# PICO_D4_SD_CARD_T3.net
KiCad netlist of a schematic drawn in Altium Designer
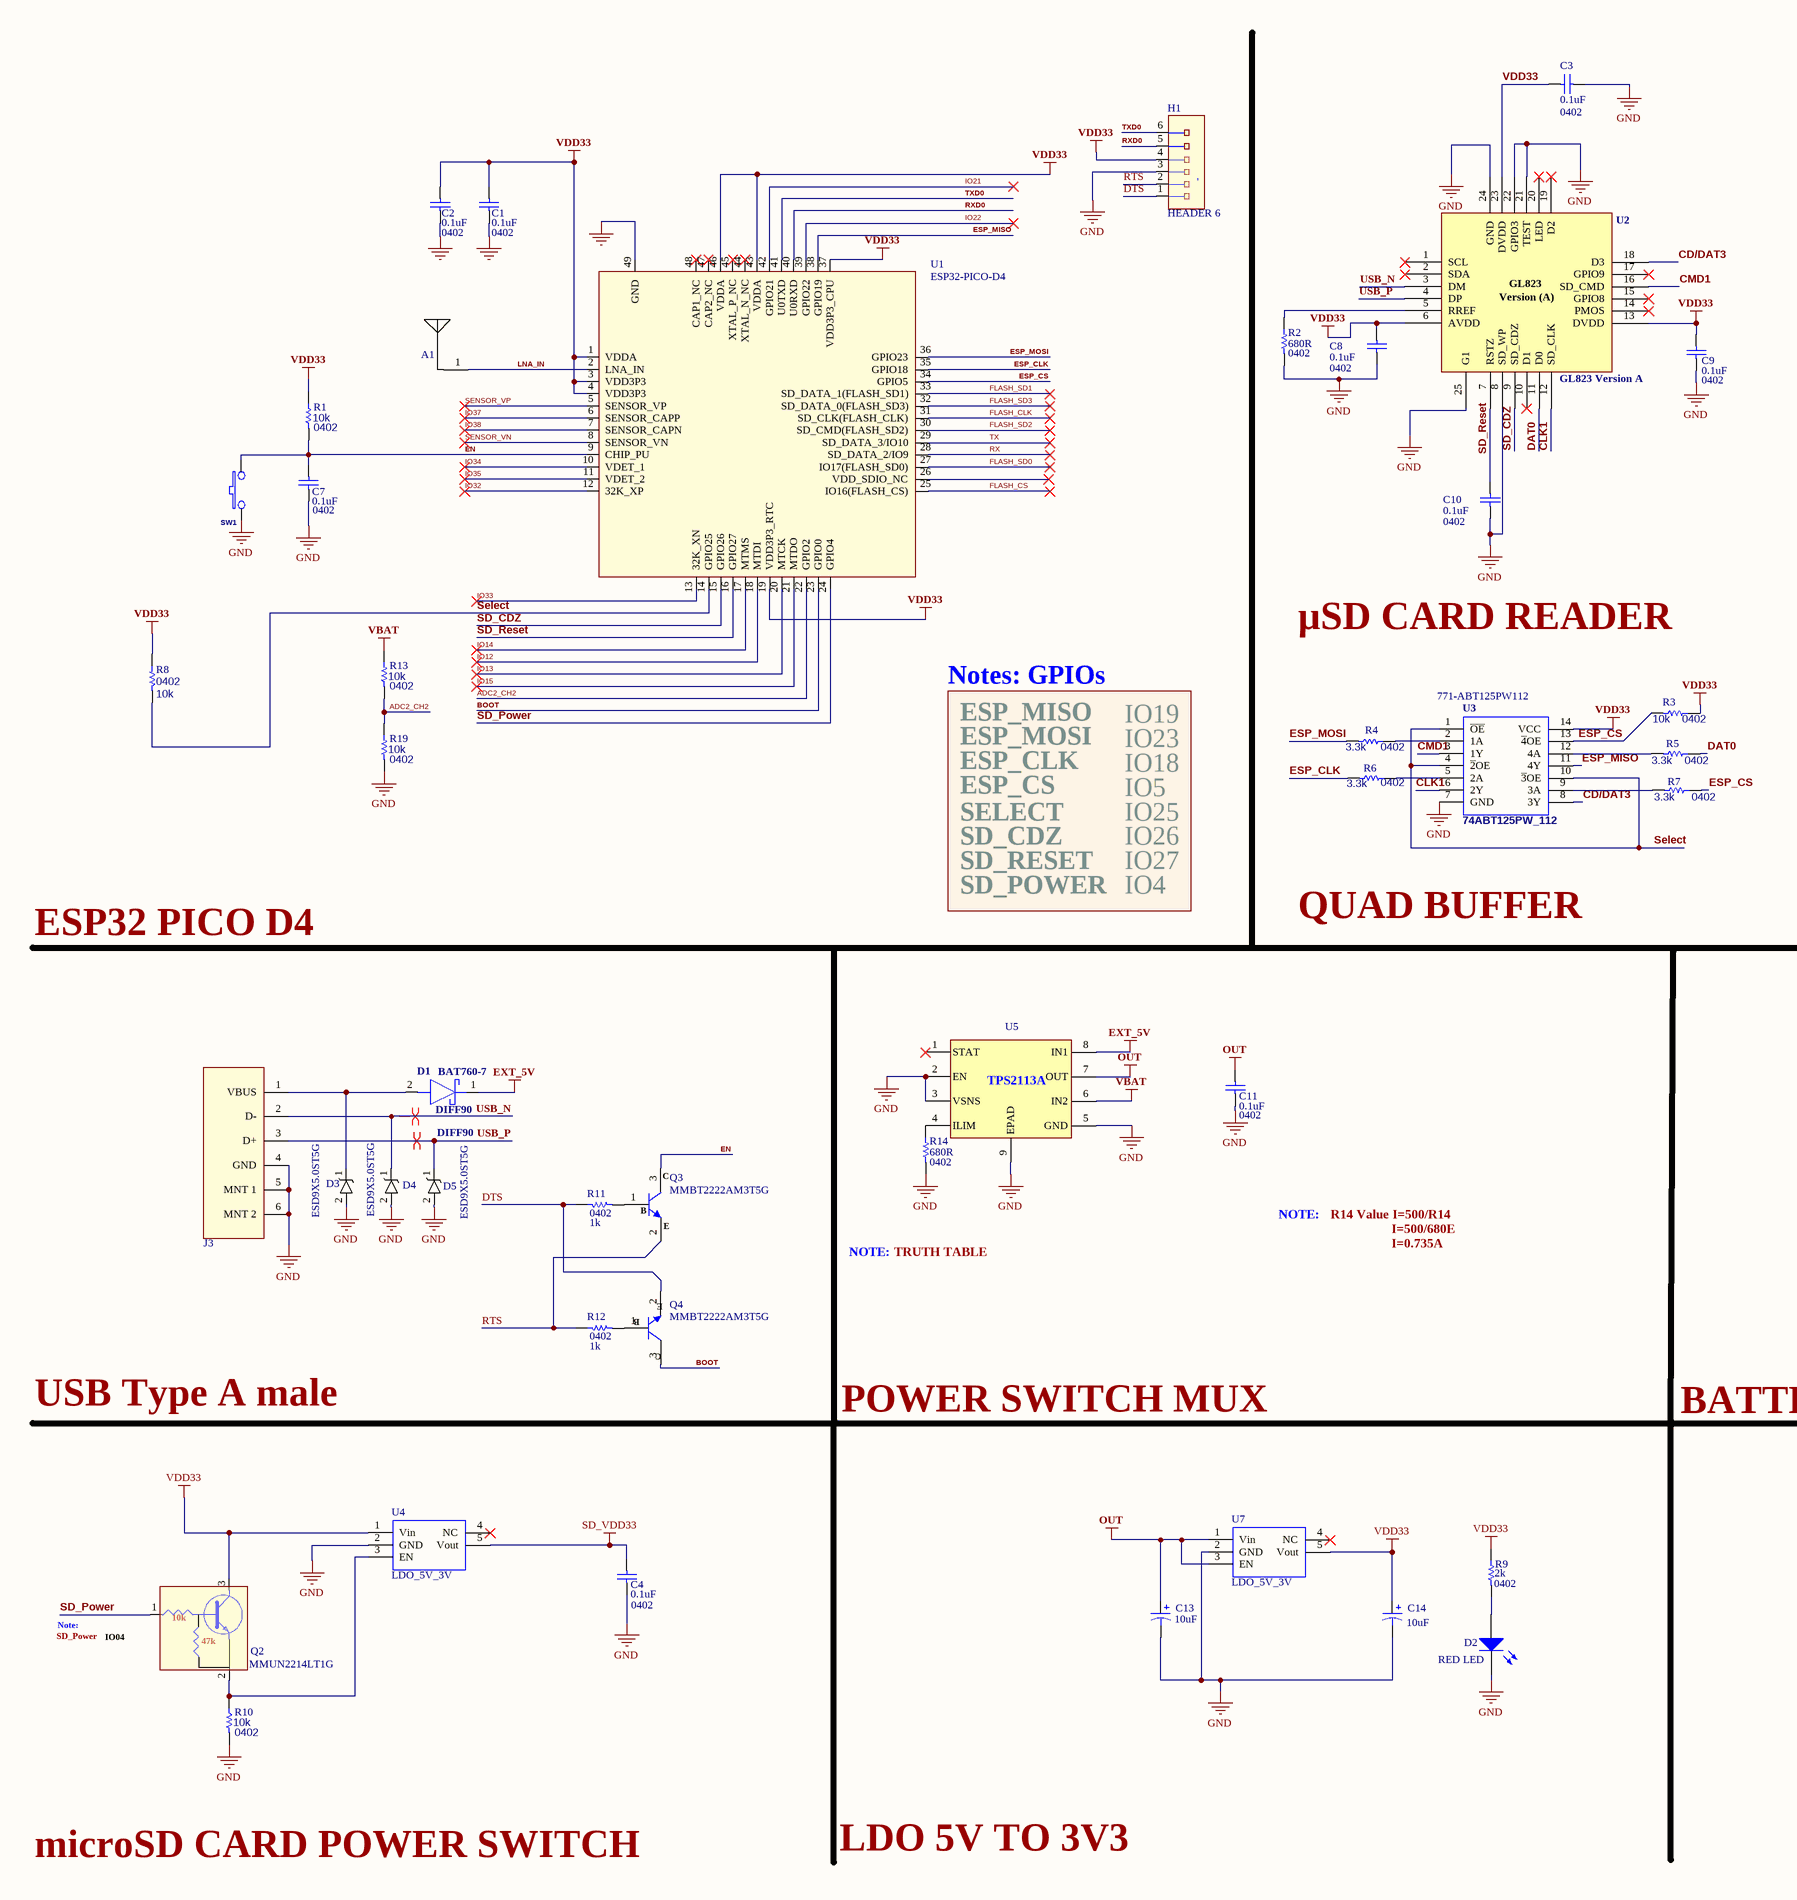
[diagram p0: PICO_D4_SD_CARD_T3.SchDoc, left]
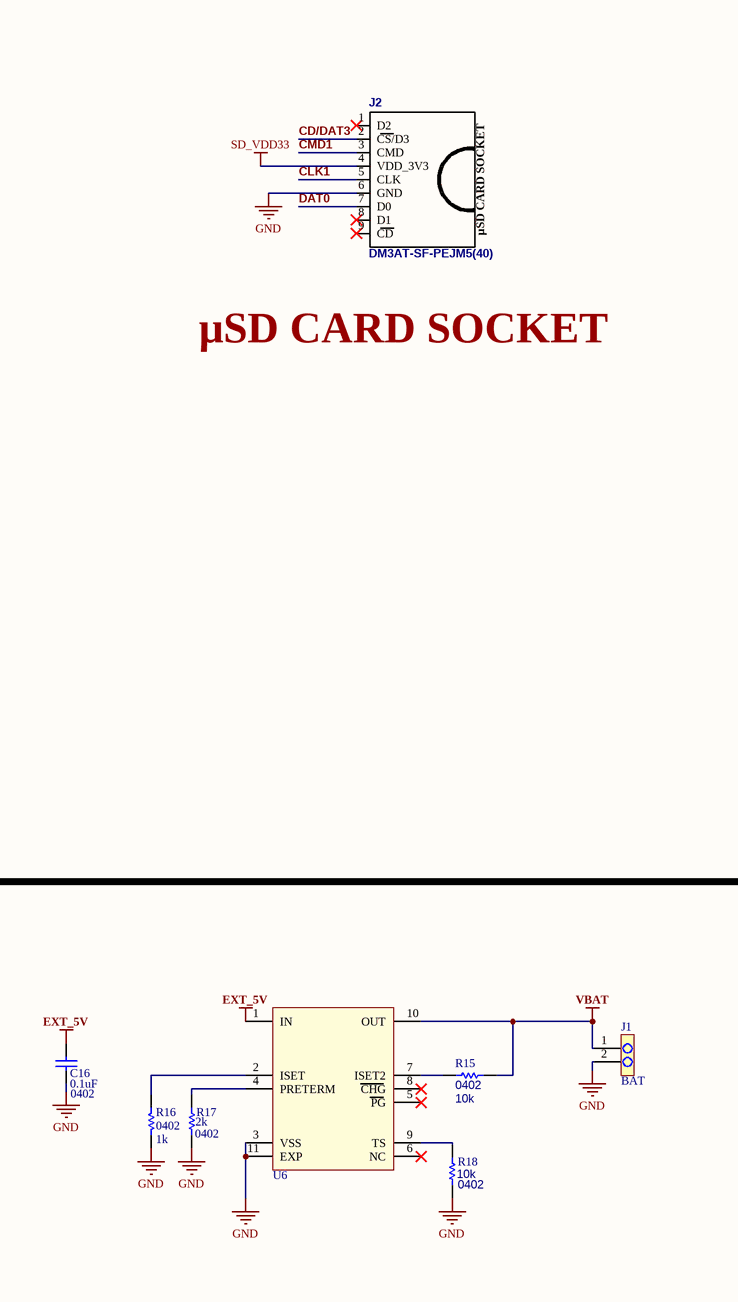
[diagram p1: PICO_D4_SD_CARD_T3.SchDoc, right]

(export (version "E")
  (design (tool "Eeschema 10.0.6"))
  (components
    (comp (ref "A1")
      (value "Ant")
      (footprint "ANT_2450AT43B100E")
      (description "High Frequency Ceramic Solutions 4-Pin SMD T/R")
      (fields
        (field (name "MANUFACTURER") "Johanson")
        (field (name "MANUFACTURER PART NUMBER") "2450AT43B100E")
      )
      (libsource (lib "CUSTOM TNY290PG") (part "Ant"))
    )
    (comp (ref "C1")
      (value "0.1uF")
      (footprint "CAPC0402")
      (description "Ceramic Capacitor,100nF,16V,0402")
      (fields
        (field (name "CASE/PACKAGE") "0402")
        (field (name "MFR.") "C0805C104K1RECAUTO")
        (field (name "MANUFACTURER") "TDK")
      )
      (libsource (lib "Miscellaneous Devices") (part "Cap"))
    )
    (comp (ref "C2")
      (value "0.1uF")
      (footprint "CAPC0402")
      (description "Ceramic Capacitor,100nF,16V,0402")
      (fields
        (field (name "CASE/PACKAGE") "0402")
        (field (name "MFR.") "C0805C104K1RECAUTO")
        (field (name "MANUFACTURER") "TDK")
      )
      (libsource (lib "Miscellaneous Devices") (part "Cap"))
    )
    (comp (ref "C3")
      (value "0.1uF")
      (footprint "CAPC0402")
      (description "Ceramic Capacitor,100nF,16V,0402")
      (fields
        (field (name "CASE/PACKAGE") "0402")
        (field (name "MFR.") "C0805C104K1RECAUTO")
        (field (name "MANUFACTURER") "TDK")
      )
      (libsource (lib "Miscellaneous Devices") (part "Cap"))
    )
    (comp (ref "C4")
      (value "0.1uF")
      (footprint "CAPC0402")
      (description "Ceramic Capacitor,100nF,16V,0402")
      (fields
        (field (name "CASE/PACKAGE") "0402")
        (field (name "MFR.") "C0805C104K1RECAUTO")
        (field (name "MANUFACTURER") "TDK")
      )
      (libsource (lib "Miscellaneous Devices") (part "Cap"))
    )
    (comp (ref "C7")
      (value "0.1uF")
      (footprint "CAPC0402")
      (description "Ceramic Capacitor,100nF,16V,0402")
      (fields
        (field (name "CASE/PACKAGE") "0402")
        (field (name "MFR.") "C0805C104K1RECAUTO")
        (field (name "MANUFACTURER") "TDK")
      )
      (libsource (lib "Miscellaneous Devices") (part "Cap"))
    )
    (comp (ref "C8")
      (value "0.1uF")
      (footprint "CAPC0402")
      (description "Ceramic Capacitor,100nF,16V,0402")
      (fields
        (field (name "CASE/PACKAGE") "0402")
        (field (name "MFR.") "C0805C104K1RECAUTO")
        (field (name "MANUFACTURER") "TDK")
      )
      (libsource (lib "Miscellaneous Devices") (part "Cap"))
    )
    (comp (ref "C9")
      (value "0.1uF")
      (footprint "CAPC0402")
      (description "Ceramic Capacitor,100nF,16V,0402")
      (fields
        (field (name "CASE/PACKAGE") "0402")
        (field (name "MFR.") "C0805C104K1RECAUTO")
        (field (name "MANUFACTURER") "TDK")
      )
      (libsource (lib "Miscellaneous Devices") (part "Cap"))
    )
    (comp (ref "C10")
      (value "0.1uF")
      (footprint "CAPC0402")
      (description "Ceramic Capacitor,100nF,16V,0402")
      (fields
        (field (name "CASE/PACKAGE") "0402")
        (field (name "MFR.") "C0805C104K1RECAUTO")
        (field (name "MANUFACTURER") "TDK")
      )
      (libsource (lib "Miscellaneous Devices") (part "Cap"))
    )
    (comp (ref "C11")
      (value "0.1uF")
      (footprint "CAPC0402")
      (description "Ceramic Capacitor,100nF,16V,0402")
      (fields
        (field (name "CASE/PACKAGE") "0402")
        (field (name "MFR.") "C0805C104K1RECAUTO")
        (field (name "MANUFACTURER") "TDK")
      )
      (libsource (lib "Miscellaneous Devices") (part "Cap"))
    )
    (comp (ref "C13")
      (value "10uF")
      (footprint "CAPC0603")
      (description "Ceramic Capacitor,10uF,16V,0603")
      (libsource (lib "Miscellaneous Devices") (part "Cap Pol2"))
    )
    (comp (ref "C14")
      (value "10uF")
      (footprint "CAPC0603")
      (description "Ceramic Capacitor,10uF,16V,0603")
      (libsource (lib "Miscellaneous Devices") (part "Cap Pol2"))
    )
    (comp (ref "C16")
      (value "0.1uF")
      (footprint "CAPC0402")
      (description "Ceramic Capacitor,100nF,16V,0402")
      (fields
        (field (name "CASE/PACKAGE") "0402")
        (field (name "MFR.") "C0805C104K1RECAUTO")
        (field (name "MANUFACTURER") "TDK")
      )
      (libsource (lib "Miscellaneous Devices") (part "Cap"))
    )
    (comp (ref "D1")
      (value "BAT760-7")
      (footprint "SOD2513X120N")
      (description "Schottky Diodes & Rectifiers 1A 30V LF1A, 2-Pin SOD-323")
      (libsource (lib "CUSTOM TNY290PG") (part "BAT760-7"))
    )
    (comp (ref "D2")
      (value "RED LED")
      (footprint "LED_0603")
      (description "LED, RED,SMD, 0603")
      (libsource (lib "Miscellaneous Devices") (part "LED1"))
    )
    (comp (ref "D3")
      (value "ESD9X5.0ST5G")
      (footprint "SOD-923")
      (description "12.3V Clamp 8.7A (8/20µs) Ipp Tvs Diode Surface Mount SOD-923")
      (fields
        (field (name "MANUFACTURER") "ON Semiconductor")
        (field (name "MANUFACTURER PART NUMBER") "ESD9X5.0ST5G")
      )
      (libsource (lib "CUSTOM TNY290PG") (part "ESD9X5.0ST5G"))
    )
    (comp (ref "D4")
      (value "ESD9X5.0ST5G")
      (footprint "SOD-923")
      (description "12.3V Clamp 8.7A (8/20µs) Ipp Tvs Diode Surface Mount SOD-923")
      (fields
        (field (name "MANUFACTURER") "ON Semiconductor")
        (field (name "MANUFACTURER PART NUMBER") "ESD9X5.0ST5G")
      )
      (libsource (lib "CUSTOM TNY290PG") (part "ESD9X5.0ST5G"))
    )
    (comp (ref "D5")
      (value "ESD9X5.0ST5G")
      (footprint "SOD-923")
      (description "12.3V Clamp 8.7A (8/20µs) Ipp Tvs Diode Surface Mount SOD-923")
      (fields
        (field (name "MANUFACTURER") "ON Semiconductor")
        (field (name "MANUFACTURER PART NUMBER") "ESD9X5.0ST5G")
      )
      (libsource (lib "CUSTOM TNY290PG") (part "ESD9X5.0ST5G"))
    )
    (comp (ref "H1")
      (value "HEADER 6")
      (footprint "HEADER_2MM")
      (description "Header, 6-Pin,2MM")
      (fields (field (name "MANUFACTURER PART NUMBER") "2mm PITCH"))
      (libsource (lib "CUSTOM TNY290PG") (part "HEADER 6"))
    )
    (comp (ref "J1")
      (value "BAT")
      (footprint "HDR1X2H - duplicate")
      (libsource (lib "CUSTOM TNY290PG") (part "Header 2 pin"))
    )
    (comp (ref "J2")
      (value "DM3AT-SF-PEJM5(40)")
      (footprint "sd card connector")
      (description "Micro SD Memory Card Socket")
      (fields
        (field (name "RS PART NUMBER") "7079520P")
        (field (name "MOUSER PART NUMBER") "798-DM3AT-SF-PEJM540")
      )
      (libsource (lib "CUSTOM TNY290PG") (part "DM3AT-SF-PEJM5(40)"))
    )
    (comp (ref "J3")
      (value "USB MALE")
      (footprint "Molex_48037-0001_0")
      (description "USB A-type Plug Male PCB R/A")
      (fields (field (name "MANUFACTURER PART NUMBER") "USB Type A male"))
      (libsource (lib "CUSTOM TNY290PG") (part "USB MALE"))
    )
    (comp (ref "Q2")
      (value "Transistor NPN")
      (footprint "SOT95P240X115-3N")
      (description "Bipolar Transistors - Pre-Biased 100mA 50V BRT NPN")
      (fields
        (field (name "MANUFACTURER") "ON Semiconductor")
        (field (name "MANUFACTURER PART NUMBER") "MMUN2214LT1G")
      )
      (libsource (lib "CUSTOM TNY290PG") (part "Transistor NPN"))
    )
    (comp (ref "Q3")
      (value "MMBT2222AM3T5G")
      (footprint "SOT-723")
      (description "Bipolar Transistors - BJT SS SOT-723 GP TRANSISTOR NPN")
      (fields (field (name "MANUFACTURER") "ON Semiconductor"))
      (libsource (lib "CUSTOM TNY290PG") (part "MMBT2222AM3T5G"))
    )
    (comp (ref "Q4")
      (value "MMBT2222AM3T5G")
      (footprint "SOT-723")
      (description "Bipolar Transistors - BJT SS SOT-723 GP TRANSISTOR NPN")
      (fields (field (name "MANUFACTURER") "ON Semiconductor"))
      (libsource (lib "CUSTOM TNY290PG") (part "MMBT2222AM3T5G"))
    )
    (comp (ref "R1")
      (value "10k")
      (footprint "resc0402")
      (description "Thick Film Resistor -  10Kohm, 1%, 0402")
      (fields
        (field (name "MANUFACTURER") "Vishay")
        (field (name "MANUFACTURER PART NUMBER") "CRCW040210K0FKED")
        (field (name "CASE/PACKAGE") "0402")
      )
      (libsource (lib "Miscellaneous Devices") (part "Res1"))
    )
    (comp (ref "R2")
      (value "680R")
      (footprint "resc0402")
      (description "Thick Film Resistor - 680 ohm, 1%, 0402")
      (fields
        (field (name "MANUFACTURER") "Panasonic")
        (field (name "MANUFACTURER PART NUMBER") "ERA-2AEB681X")
        (field (name "CASE/PACKAGE") "0402")
      )
      (libsource (lib "Miscellaneous Devices") (part "Res1"))
    )
    (comp (ref "R3")
      (value "10k")
      (footprint "resc0402")
      (description "Thick Film Resistor -  10Kohm, 1%, 0402")
      (fields
        (field (name "MANUFACTURER") "Vishay")
        (field (name "MANUFACTURER PART NUMBER") "CRCW040210K0FKED")
        (field (name "CASE/PACKAGE") "0402")
      )
      (libsource (lib "Miscellaneous Devices") (part "Res1"))
    )
    (comp (ref "R4")
      (value "3.3k")
      (footprint "RESC0402")
      (description "Thick Film Resistor - 3.3 Kohm, 1%, 0402")
      (fields
        (field (name "MANUFACTURER") "Vishay Dale")
        (field (name "MANUFACTURER PART NUMBER") "CRCW04023K30JNED")
        (field (name "CASE/PACKAGE") "0402")
      )
      (libsource (lib "Miscellaneous Devices") (part "Res1"))
    )
    (comp (ref "R5")
      (value "3.3k")
      (footprint "RESC0402")
      (description "Thick Film Resistor - 3.3 Kohm, 1%, 0402")
      (fields
        (field (name "MANUFACTURER") "Vishay Dale")
        (field (name "MANUFACTURER PART NUMBER") "CRCW04023K30JNED")
        (field (name "CASE/PACKAGE") "0402")
      )
      (libsource (lib "Miscellaneous Devices") (part "Res1"))
    )
    (comp (ref "R6")
      (value "3.3k")
      (footprint "RESC0402")
      (description "Thick Film Resistor - 3.3 Kohm, 1%, 0402")
      (fields
        (field (name "MANUFACTURER") "Vishay Dale")
        (field (name "MANUFACTURER PART NUMBER") "CRCW04023K30JNED")
        (field (name "CASE/PACKAGE") "0402")
      )
      (libsource (lib "Miscellaneous Devices") (part "Res1"))
    )
    (comp (ref "R7")
      (value "3.3k")
      (footprint "RESC0402")
      (description "Thick Film Resistor - 3.3 Kohm, 1%, 0402")
      (fields
        (field (name "MANUFACTURER") "Vishay Dale")
        (field (name "MANUFACTURER PART NUMBER") "CRCW04023K30JNED")
        (field (name "CASE/PACKAGE") "0402")
      )
      (libsource (lib "Miscellaneous Devices") (part "Res1"))
    )
    (comp (ref "R8")
      (value "10k")
      (footprint "resc0402")
      (description "Thick Film Resistor -  10Kohm, 1%, 0402")
      (fields
        (field (name "MANUFACTURER") "Vishay")
        (field (name "MANUFACTURER PART NUMBER") "CRCW040210K0FKED")
        (field (name "CASE/PACKAGE") "0402")
      )
      (libsource (lib "Miscellaneous Devices") (part "Res1"))
    )
    (comp (ref "R9")
      (value "2k")
      (footprint "resc0402")
      (description "Thick Film Resistor -  2Kohm, 1%, 0402")
      (fields
        (field (name "MANUFACTURER") "Vishay Semiconductors")
        (field (name "MANUFACTURER PART NUMBER") "CRCW04022K00FKEDC")
        (field (name "CASE/PACKAGE") "0402")
      )
      (libsource (lib "Miscellaneous Devices") (part "Res1"))
    )
    (comp (ref "R10")
      (value "10k")
      (footprint "resc0402")
      (description "Thick Film Resistor -  10Kohm, 1%, 0402")
      (fields
        (field (name "MANUFACTURER") "Vishay")
        (field (name "MANUFACTURER PART NUMBER") "CRCW040210K0FKED")
        (field (name "CASE/PACKAGE") "0402")
      )
      (libsource (lib "Miscellaneous Devices") (part "Res1"))
    )
    (comp (ref "R11")
      (value "1k")
      (footprint "resc0402")
      (description "Thick Film Resistor -  1Kohm, 1%, 0402")
      (fields
        (field (name "MANUFACTURER") "TE Connectivity")
        (field (name "MANUFACTURER PART NUMBER") "CRGCQ0402F1K0")
        (field (name "CASE/PACKAGE") "0402")
      )
      (libsource (lib "Miscellaneous Devices") (part "Res1"))
    )
    (comp (ref "R12")
      (value "1k")
      (footprint "resc0402")
      (description "Thick Film Resistor -  1Kohm, 1%, 0402")
      (fields
        (field (name "MANUFACTURER") "TE Connectivity")
        (field (name "MANUFACTURER PART NUMBER") "CRGCQ0402F1K0")
        (field (name "CASE/PACKAGE") "0402")
      )
      (libsource (lib "Miscellaneous Devices") (part "Res1"))
    )
    (comp (ref "R13")
      (value "10k")
      (footprint "resc0402")
      (description "Thick Film Resistor -  10Kohm, 1%, 0402")
      (fields
        (field (name "MANUFACTURER") "Vishay")
        (field (name "MANUFACTURER PART NUMBER") "CRCW040210K0FKED")
        (field (name "CASE/PACKAGE") "0402")
      )
      (libsource (lib "Miscellaneous Devices") (part "Res1"))
    )
    (comp (ref "R14")
      (value "680R")
      (footprint "resc0402")
      (description "Thick Film Resistor - 680 ohm, 1%, 0402")
      (fields
        (field (name "MANUFACTURER") "Panasonic")
        (field (name "MANUFACTURER PART NUMBER") "ERA-2AEB681X")
        (field (name "CASE/PACKAGE") "0402")
      )
      (libsource (lib "Miscellaneous Devices") (part "Res1"))
    )
    (comp (ref "R15")
      (value "10k")
      (footprint "resc0402")
      (description "Thick Film Resistor -  10Kohm, 1%, 0402")
      (fields
        (field (name "MANUFACTURER") "Vishay")
        (field (name "MANUFACTURER PART NUMBER") "CRCW040210K0FKED")
        (field (name "CASE/PACKAGE") "0402")
      )
      (libsource (lib "Miscellaneous Devices") (part "Res1"))
    )
    (comp (ref "R16")
      (value "1k")
      (footprint "resc0402")
      (description "Thick Film Resistor -  1Kohm, 1%, 0402")
      (fields
        (field (name "MANUFACTURER") "TE Connectivity")
        (field (name "MANUFACTURER PART NUMBER") "CRGCQ0402F1K0")
        (field (name "CASE/PACKAGE") "0402")
      )
      (libsource (lib "Miscellaneous Devices") (part "Res1"))
    )
    (comp (ref "R17")
      (value "2k")
      (footprint "resc0402")
      (description "Thick Film Resistor -  2Kohm, 1%, 0402")
      (fields
        (field (name "MANUFACTURER") "Vishay Semiconductors")
        (field (name "MANUFACTURER PART NUMBER") "CRCW04022K00FKEDC")
        (field (name "CASE/PACKAGE") "0402")
      )
      (libsource (lib "Miscellaneous Devices") (part "Res1"))
    )
    (comp (ref "R18")
      (value "10k")
      (footprint "resc0402")
      (description "Thick Film Resistor -  10Kohm, 1%, 0402")
      (fields
        (field (name "MANUFACTURER") "Vishay")
        (field (name "MANUFACTURER PART NUMBER") "CRCW040210K0FKED")
        (field (name "CASE/PACKAGE") "0402")
      )
      (libsource (lib "Miscellaneous Devices") (part "Res1"))
    )
    (comp (ref "R19")
      (value "10k")
      (footprint "resc0402")
      (description "Thick Film Resistor -  10Kohm, 1%, 0402")
      (fields
        (field (name "MANUFACTURER") "Vishay")
        (field (name "MANUFACTURER PART NUMBER") "CRCW040210K0FKED")
        (field (name "CASE/PACKAGE") "0402")
      )
      (libsource (lib "Miscellaneous Devices") (part "Res1"))
    )
    (comp (ref "SW1")
      (value "SW PUSHBUTTON")
      (footprint "Micro_push")
      (description "Tactile Switch 3x4x2mm SMD 2-Pin")
      (fields (field (name "MANUFACTURER PART NUMBER") "3x4x2mm switch"))
      (libsource (lib "*") (part "SW PUSHBUTTON"))
    )
    (comp (ref "U1")
      (value "ESP32-PICO-D4")
      (footprint "ESP32_PICO_D4_2")
      (description "RF System on a Chip - SoC SIP module ESP32 with 4MByte Flash")
      (libsource (lib "CUSTOM TNY290PG") (part "ESP8080_1"))
    )
    (comp (ref "U2")
      (value "GL823 Version A")
      (footprint "QFN24-4x4MM")
      (description "USB 2.0 SD/MMC Card Reader Controller version A")
      (fields (field (name "MANUFACTURER PART NUMBER") "GL823 VERSION A"))
      (libsource (lib "CUSTOM TNY290PG") (part "GL823"))
    )
    (comp (ref "U3")
      (value "74ABT125PW_112")
      (footprint "74ABT125PW")
      (description "Buffers & Line Drivers QUAD BUFFER 3-S")
      (fields
        (field (name "SUPPLIER PART NUMBER 1") "771-ABT125PW112")
        (field (name "MANUFACTURER") "NXP Semiconductors")
        (field (name "MANUFACTURER PART NUMBER") "74ABT125PW,112")
      )
      (libsource (lib "CUSTOM TNY290PG") (part "74ABT125PW_112"))
    )
    (comp (ref "U4")
      (value "LDO_5V_3V")
      (footprint "SOT25")
      (description "LDO Voltage Regulators 600mA CMOS LDO 50mA 3.3V 250mV")
      (fields
        (field (name "MANUFACTURER") "Diodes")
        (field (name "MANUFACTURER PART NUMBER") "AP2112K-3.3TRG1")
      )
      (libsource (lib "VEGG_Schlib") (part "LDO_5V_3V"))
    )
    (comp (ref "U5")
      (value "TPS2113ADRBR")
      (footprint "SON-8")
      (description "Power Switch ICs -Autoswitching Pwr Mux 3-mm × 3-mm SON-8")
      (fields (field (name "MANUFACTURER") "Texas Instruments"))
      (libsource (lib "CUSTOM TNY290PG") (part "TPS2113ADRBR"))
    )
    (comp (ref "U6")
      (value "BQ24040DSQR")
      (footprint "10-WFDFN")
      (description "IC BATT CHG LI-ION 1 CELL 10SON")
      (fields (field (name "MANUFACTURER") "Texas Instruments"))
      (libsource (lib "CUSTOM TNY290PG") (part "BQ24040DSQR"))
    )
    (comp (ref "U7")
      (value "LDO_5V_3V")
      (footprint "SOT25")
      (description "LDO Voltage Regulators 600mA CMOS LDO 50mA 3.3V 250mV")
      (fields
        (field (name "MANUFACTURER") "Diodes")
        (field (name "MANUFACTURER PART NUMBER") "AP2112K-3.3TRG1")
      )
      (libsource (lib "VEGG_Schlib") (part "LDO_5V_3V"))
    )
  )
  (nets
    (net (code "1") (name "/ADC2_CH2") (class "Default")
      (node (ref "R13") (pin "2") (pinfunction "2_2") (pintype "passive"))
      (node (ref "R19") (pin "1") (pinfunction "1_1") (pintype "passive"))
      (node (ref "U1") (pin "22") (pinfunction "GPIO2_22") (pintype "passive"))
    )
    (net (code "2") (name "/BOOT") (class "Default")
      (node (ref "Q4") (pin "3") (pinfunction "C_3") (pintype "passive"))
      (node (ref "U1") (pin "23") (pinfunction "GPIO0_23") (pintype "passive"))
    )
    (net (code "3") (name "/CD{slash}DAT3") (class "Default")
      (node (ref "J2") (pin "2") (pinfunction "CS/D3_2") (pintype "passive"))
      (node (ref "U2") (pin "18") (pinfunction "D3_18") (pintype "passive"))
      (node (ref "U3") (pin "8") (pinfunction "3Y_8") (pintype "passive"))
    )
    (net (code "4") (name "/CLK1") (class "Default")
      (node (ref "J2") (pin "5") (pinfunction "CLK_5") (pintype "passive"))
      (node (ref "U2") (pin "12") (pinfunction "SD_CLK_12") (pintype "passive"))
      (node (ref "U3") (pin "6") (pinfunction "2Y_6") (pintype "passive"))
    )
    (net (code "5") (name "/CMD1") (class "Default")
      (node (ref "J2") (pin "3") (pinfunction "CMD_3") (pintype "passive"))
      (node (ref "U2") (pin "16") (pinfunction "SD_CMD_16") (pintype "passive"))
      (node (ref "U3") (pin "3") (pinfunction "1Y_3") (pintype "passive"))
    )
    (net (code "6") (name "/DAT0") (class "Default")
      (node (ref "J2") (pin "7") (pinfunction "D0_7") (pintype "passive"))
      (node (ref "R5") (pin "1") (pinfunction "1_1") (pintype "passive"))
      (node (ref "U2") (pin "11") (pinfunction "D0_11") (pintype "passive"))
    )
    (net (code "7") (name "/DTS") (class "Default")
      (node (ref "H1") (pin "1") (pinfunction "1_1") (pintype "passive"))
      (node (ref "Q4") (pin "2") (pinfunction "E_2") (pintype "passive"))
      (node (ref "R11") (pin "1") (pinfunction "1_1") (pintype "passive"))
    )
    (net (code "8") (name "/EN") (class "Default")
      (node (ref "C7") (pin "2") (pinfunction "2_2") (pintype "passive"))
      (node (ref "Q3") (pin "3") (pinfunction "C_3") (pintype "passive"))
      (node (ref "R1") (pin "2") (pinfunction "2_2") (pintype "passive"))
      (node (ref "SW1") (pin "2") (pinfunction "2_2") (pintype "passive"))
      (node (ref "U1") (pin "9") (pinfunction "CHIP_PU_9") (pintype "passive"))
    )
    (net (code "9") (name "/ESP_CLK") (class "Default")
      (node (ref "R6") (pin "2") (pinfunction "2_2") (pintype "passive"))
      (node (ref "U1") (pin "35") (pinfunction "GPIO18_35") (pintype "passive"))
    )
    (net (code "10") (name "/ESP_CS") (class "Default")
      (node (ref "R3") (pin "2") (pinfunction "2_2") (pintype "passive"))
      (node (ref "R7") (pin "1") (pinfunction "1_1") (pintype "passive"))
      (node (ref "U1") (pin "34") (pinfunction "GPIO5_34") (pintype "passive"))
      (node (ref "U3") (pin "13") (pinfunction "~{4}OE_13") (pintype "passive"))
    )
    (net (code "11") (name "/ESP_MISO") (class "Default")
      (node (ref "U1") (pin "38") (pinfunction "GPIO19_38") (pintype "passive"))
      (node (ref "U3") (pin "11") (pinfunction "4Y_11") (pintype "passive"))
    )
    (net (code "12") (name "/ESP_MOSI") (class "Default")
      (node (ref "R4") (pin "2") (pinfunction "2_2") (pintype "passive"))
      (node (ref "U1") (pin "36") (pinfunction "GPIO23_36") (pintype "passive"))
    )
    (net (code "13") (name "/FLASH_CLK") (class "Default")
      (node (ref "U1") (pin "31") (pinfunction "SD_CLK(FLASH_CLK)_31") (pintype "passive+no_connect"))
    )
    (net (code "14") (name "/FLASH_CS") (class "Default")
      (node (ref "U1") (pin "25") (pinfunction "IO16(FLASH_CS)_25") (pintype "passive+no_connect"))
    )
    (net (code "15") (name "/FLASH_SD0") (class "Default")
      (node (ref "U1") (pin "27") (pinfunction "IO17(FLASH_SD0)_27") (pintype "passive+no_connect"))
    )
    (net (code "16") (name "/FLASH_SD1") (class "Default")
      (node (ref "U1") (pin "33") (pinfunction "SD_DATA_1(FLASH_SD1)_33") (pintype "passive+no_connect"))
    )
    (net (code "17") (name "/FLASH_SD2") (class "Default")
      (node (ref "U1") (pin "30") (pinfunction "SD_CMD(FLASH_SD2)_30") (pintype "passive+no_connect"))
    )
    (net (code "18") (name "/FLASH_SD3") (class "Default")
      (node (ref "U1") (pin "32") (pinfunction "SD_DATA_0(FLASH_SD3)_32") (pintype "passive+no_connect"))
    )
    (net (code "19") (name "/IO12") (class "Default")
      (node (ref "U1") (pin "18") (pinfunction "MTDI_18") (pintype "passive+no_connect"))
    )
    (net (code "20") (name "/IO13") (class "Default")
      (node (ref "U1") (pin "20") (pinfunction "MTCK_20") (pintype "passive+no_connect"))
    )
    (net (code "21") (name "/IO14") (class "Default")
      (node (ref "U1") (pin "17") (pinfunction "MTMS_17") (pintype "passive+no_connect"))
    )
    (net (code "22") (name "/IO15") (class "Default")
      (node (ref "U1") (pin "21") (pinfunction "MTDO_21") (pintype "passive+no_connect"))
    )
    (net (code "23") (name "/IO21") (class "Default")
      (node (ref "U1") (pin "42") (pinfunction "GPIO21_42") (pintype "passive+no_connect"))
    )
    (net (code "24") (name "/IO22") (class "Default")
      (node (ref "U1") (pin "39") (pinfunction "GPIO22_39") (pintype "passive+no_connect"))
    )
    (net (code "25") (name "/IO32") (class "Default")
      (node (ref "U1") (pin "12") (pinfunction "32K_XP_12") (pintype "passive+no_connect"))
    )
    (net (code "26") (name "/IO33") (class "Default")
      (node (ref "U1") (pin "13") (pinfunction "32K_XN_13") (pintype "passive+no_connect"))
    )
    (net (code "27") (name "/IO34") (class "Default")
      (node (ref "U1") (pin "10") (pinfunction "VDET_1_10") (pintype "passive+no_connect"))
    )
    (net (code "28") (name "/IO35") (class "Default")
      (node (ref "U1") (pin "11") (pinfunction "VDET_2_11") (pintype "passive+no_connect"))
    )
    (net (code "29") (name "/IO37") (class "Default")
      (node (ref "U1") (pin "6") (pinfunction "SENSOR_CAPP_6") (pintype "passive+no_connect"))
    )
    (net (code "30") (name "/IO38") (class "Default")
      (node (ref "U1") (pin "7") (pinfunction "SENSOR_CAPN_7") (pintype "passive+no_connect"))
    )
    (net (code "31") (name "/LNA_IN") (class "Default")
      (node (ref "A1") (pin "1") (pinfunction "Ant_1") (pintype "passive"))
      (node (ref "U1") (pin "2") (pinfunction "LNA_IN_2") (pintype "passive"))
    )
    (net (code "32") (name "/RTS") (class "Default")
      (node (ref "H1") (pin "2") (pinfunction "2_2") (pintype "passive"))
      (node (ref "Q3") (pin "2") (pinfunction "E_2") (pintype "passive"))
      (node (ref "R12") (pin "1") (pinfunction "1_1") (pintype "passive"))
    )
    (net (code "33") (name "/RX") (class "Default")
      (node (ref "U1") (pin "28") (pinfunction "SD_DATA_2/IO9_28") (pintype "passive+no_connect"))
    )
    (net (code "34") (name "/RXD0") (class "Default")
      (node (ref "H1") (pin "5") (pinfunction "4_5") (pintype "passive"))
      (node (ref "U1") (pin "40") (pinfunction "U0RXD_40") (pintype "power_in"))
    )
    (net (code "35") (name "/SD_CDZ") (class "Default")
      (node (ref "U1") (pin "15") (pinfunction "GPIO26_15") (pintype "passive"))
      (node (ref "U2") (pin "9") (pinfunction "SD_CDZ_9") (pintype "passive"))
    )
    (net (code "36") (name "/SD_Power") (class "Default")
      (node (ref "Q2") (pin "1") (pinfunction "B_1") (pintype "passive"))
      (node (ref "U1") (pin "24") (pinfunction "GPIO4_24") (pintype "passive"))
    )
    (net (code "37") (name "/SD_Reset") (class "Default")
      (node (ref "C10") (pin "2") (pinfunction "2_2") (pintype "passive"))
      (node (ref "U1") (pin "16") (pinfunction "GPIO27_16") (pintype "passive"))
      (node (ref "U2") (pin "7") (pinfunction "RSTZ_7") (pintype "passive"))
    )
    (net (code "38") (name "/SENSOR_VN") (class "Default")
      (node (ref "U1") (pin "8") (pinfunction "SENSOR_VN_8") (pintype "passive+no_connect"))
    )
    (net (code "39") (name "/SENSOR_VP") (class "Default")
      (node (ref "U1") (pin "5") (pinfunction "SENSOR_VP_5") (pintype "passive+no_connect"))
    )
    (net (code "40") (name "/Select") (class "Default")
      (node (ref "R8") (pin "2") (pinfunction "2_2") (pintype "passive"))
      (node (ref "U1") (pin "14") (pinfunction "GPIO25_14") (pintype "passive"))
      (node (ref "U3") (pin "1") (pinfunction "OE_1") (pintype "passive"))
      (node (ref "U3") (pin "10") (pinfunction "~{3}OE_10") (pintype "passive"))
      (node (ref "U3") (pin "4") (pinfunction "~{2}OE_4") (pintype "passive"))
    )
    (net (code "41") (name "/TX") (class "Default")
      (node (ref "U1") (pin "29") (pinfunction "SD_DATA_3/IO10_29") (pintype "passive+no_connect"))
    )
    (net (code "42") (name "/TXD0") (class "Default")
      (node (ref "H1") (pin "6") (pinfunction "6_6") (pintype "passive"))
      (node (ref "U1") (pin "41") (pinfunction "U0TXD_41") (pintype "power_in"))
    )
    (net (code "43") (name "/USB_N") (class "Default")
      (node (ref "D4") (pin "1") (pinfunction "K_1") (pintype "passive"))
      (node (ref "J3") (pin "2") (pinfunction "D-_2") (pintype "passive"))
      (node (ref "U2") (pin "3") (pinfunction "DM_3") (pintype "passive"))
    )
    (net (code "44") (name "/USB_P") (class "Default")
      (node (ref "D5") (pin "1") (pinfunction "K_1") (pintype "passive"))
      (node (ref "J3") (pin "3") (pinfunction "D+_3") (pintype "passive"))
      (node (ref "U2") (pin "4") (pinfunction "DP_4") (pintype "passive"))
    )
    (net (code "45") (name "EXT_5V") (class "Default")
      (node (ref "C16") (pin "2") (pinfunction "2_2") (pintype "passive"))
      (node (ref "D1") (pin "1") (pinfunction "K_1") (pintype "passive"))
      (node (ref "U5") (pin "8") (pinfunction "IN1_8") (pintype "passive"))
      (node (ref "U6") (pin "1") (pinfunction "IN_1") (pintype "passive"))
    )
    (net (code "46") (name "GND") (class "Default")
      (node (ref "C1") (pin "2") (pinfunction "2_2") (pintype "passive"))
      (node (ref "C10") (pin "1") (pinfunction "1_1") (pintype "passive"))
      (node (ref "C11") (pin "1") (pinfunction "1_1") (pintype "passive"))
      (node (ref "C13") (pin "2") (pinfunction "2_2") (pintype "passive"))
      (node (ref "C14") (pin "2") (pinfunction "2_2") (pintype "passive"))
      (node (ref "C16") (pin "1") (pinfunction "1_1") (pintype "passive"))
      (node (ref "C2") (pin "2") (pinfunction "2_2") (pintype "passive"))
      (node (ref "C3") (pin "1") (pinfunction "1_1") (pintype "passive"))
      (node (ref "C4") (pin "2") (pinfunction "2_2") (pintype "passive"))
      (node (ref "C7") (pin "1") (pinfunction "1_1") (pintype "passive"))
      (node (ref "C8") (pin "1") (pinfunction "1_1") (pintype "passive"))
      (node (ref "C9") (pin "1") (pinfunction "1_1") (pintype "passive"))
      (node (ref "D2") (pin "2") (pinfunction "K_2") (pintype "passive"))
      (node (ref "D3") (pin "2") (pinfunction "A_2") (pintype "passive"))
      (node (ref "D4") (pin "2") (pinfunction "A_2") (pintype "passive"))
      (node (ref "D5") (pin "2") (pinfunction "A_2") (pintype "passive"))
      (node (ref "H1") (pin "3") (pinfunction "3_3") (pintype "passive"))
      (node (ref "J1") (pin "2") (pinfunction "2_2") (pintype "passive"))
      (node (ref "J2") (pin "6") (pinfunction "GND_6") (pintype "passive"))
      (node (ref "J3") (pin "4") (pinfunction "GND_4") (pintype "passive"))
      (node (ref "J3") (pin "5") (pinfunction "MNT_1_5") (pintype "passive"))
      (node (ref "J3") (pin "6") (pinfunction "MNT_2_6") (pintype "passive"))
      (node (ref "R10") (pin "2") (pinfunction "2_2") (pintype "passive"))
      (node (ref "R14") (pin "2") (pinfunction "2_2") (pintype "passive"))
      (node (ref "R16") (pin "1") (pinfunction "1_1") (pintype "passive"))
      (node (ref "R17") (pin "2") (pinfunction "2_2") (pintype "passive"))
      (node (ref "R18") (pin "2") (pinfunction "2_2") (pintype "passive"))
      (node (ref "R19") (pin "2") (pinfunction "2_2") (pintype "passive"))
      (node (ref "R2") (pin "2") (pinfunction "2_2") (pintype "passive"))
      (node (ref "SW1") (pin "1") (pinfunction "1_1") (pintype "passive"))
      (node (ref "U1") (pin "49") (pinfunction "GND_49") (pintype "power_in"))
      (node (ref "U2") (pin "21") (pinfunction "TEST_21") (pintype "passive"))
      (node (ref "U2") (pin "22") (pinfunction "GPIO3_22") (pintype "passive"))
      (node (ref "U2") (pin "24") (pinfunction "GND_24") (pintype "passive"))
      (node (ref "U2") (pin "25") (pinfunction "G1_25") (pintype "passive"))
      (node (ref "U2") (pin "8") (pinfunction "SD_WP_8") (pintype "passive"))
      (node (ref "U3") (pin "7") (pinfunction "GND_7") (pintype "passive"))
      (node (ref "U4") (pin "2") (pinfunction "GND_2") (pintype "power_in"))
      (node (ref "U5") (pin "2") (pinfunction "EN_2") (pintype "passive"))
      (node (ref "U5") (pin "3") (pinfunction "VSNS_3") (pintype "passive"))
      (node (ref "U5") (pin "5") (pinfunction "GND_5") (pintype "passive"))
      (node (ref "U5") (pin "9") (pinfunction "EPAD_9") (pintype "passive"))
      (node (ref "U6") (pin "11") (pinfunction "EXP_11") (pintype "passive"))
      (node (ref "U6") (pin "3") (pinfunction "VSS_3") (pintype "passive"))
      (node (ref "U7") (pin "2") (pinfunction "GND_2") (pintype "power_in"))
    )
    (net (code "47") (name "Net-(D1-A)") (class "Default")
      (node (ref "D1") (pin "2") (pinfunction "A_2") (pintype "passive"))
      (node (ref "D3") (pin "1") (pinfunction "K_1") (pintype "passive"))
      (node (ref "J3") (pin "1") (pinfunction "VBUS_1") (pintype "passive"))
    )
    (net (code "48") (name "Net-(D2-A)") (class "Default")
      (node (ref "D2") (pin "1") (pinfunction "A_1") (pintype "passive"))
      (node (ref "R9") (pin "2") (pinfunction "2_2") (pintype "passive"))
    )
    (net (code "49") (name "Net-(Q2-E)") (class "Default")
      (node (ref "Q2") (pin "2") (pinfunction "E_2") (pintype "passive"))
      (node (ref "R10") (pin "1") (pinfunction "1_1") (pintype "passive"))
      (node (ref "U4") (pin "3") (pinfunction "EN_3") (pintype "passive"))
    )
    (net (code "50") (name "Net-(Q3-B)") (class "Default")
      (node (ref "Q3") (pin "1") (pinfunction "B_1") (pintype "passive"))
      (node (ref "R11") (pin "2") (pinfunction "2_2") (pintype "passive"))
    )
    (net (code "51") (name "Net-(Q4-B)") (class "Default")
      (node (ref "Q4") (pin "1") (pinfunction "B_1") (pintype "passive"))
      (node (ref "R12") (pin "2") (pinfunction "2_2") (pintype "passive"))
    )
    (net (code "52") (name "Net-(U2-RREF)") (class "Default")
      (node (ref "R2") (pin "1") (pinfunction "1_1") (pintype "passive"))
      (node (ref "U2") (pin "5") (pinfunction "RREF_5") (pintype "passive"))
    )
    (net (code "53") (name "Net-(U3-1A)") (class "Default")
      (node (ref "R4") (pin "1") (pinfunction "1_1") (pintype "passive"))
      (node (ref "U3") (pin "2") (pinfunction "1A_2") (pintype "passive"))
    )
    (net (code "54") (name "Net-(U3-2A)") (class "Default")
      (node (ref "R6") (pin "1") (pinfunction "1_1") (pintype "passive"))
      (node (ref "U3") (pin "5") (pinfunction "2A_5") (pintype "passive"))
    )
    (net (code "55") (name "Net-(U3-3A)") (class "Default")
      (node (ref "R7") (pin "2") (pinfunction "2_2") (pintype "passive"))
      (node (ref "U3") (pin "9") (pinfunction "3A_9") (pintype "passive"))
    )
    (net (code "56") (name "Net-(U3-4A)") (class "Default")
      (node (ref "R5") (pin "2") (pinfunction "2_2") (pintype "passive"))
      (node (ref "U3") (pin "12") (pinfunction "4A_12") (pintype "passive"))
    )
    (net (code "57") (name "Net-(U5-ILIM)") (class "Default")
      (node (ref "R14") (pin "1") (pinfunction "1_1") (pintype "passive"))
      (node (ref "U5") (pin "4") (pinfunction "ILIM_4") (pintype "passive"))
    )
    (net (code "58") (name "Net-(U6-ISET)") (class "Default")
      (node (ref "R16") (pin "2") (pinfunction "2_2") (pintype "passive"))
      (node (ref "U6") (pin "2") (pinfunction "ISET_2") (pintype "passive"))
    )
    (net (code "59") (name "Net-(U6-ISET2)") (class "Default")
      (node (ref "R15") (pin "1") (pinfunction "1_1") (pintype "passive"))
      (node (ref "U6") (pin "7") (pinfunction "ISET2_7") (pintype "passive"))
    )
    (net (code "60") (name "Net-(U6-PRETERM)") (class "Default")
      (node (ref "R17") (pin "1") (pinfunction "1_1") (pintype "passive"))
      (node (ref "U6") (pin "4") (pinfunction "PRETERM_4") (pintype "passive"))
    )
    (net (code "61") (name "Net-(U6-TS)") (class "Default")
      (node (ref "R18") (pin "1") (pinfunction "1_1") (pintype "passive"))
      (node (ref "U6") (pin "9") (pinfunction "TS_9") (pintype "passive"))
    )
    (net (code "62") (name "OUT") (class "Default")
      (node (ref "C11") (pin "2") (pinfunction "2_2") (pintype "passive"))
      (node (ref "C13") (pin "1") (pinfunction "1_1") (pintype "passive"))
      (node (ref "U5") (pin "7") (pinfunction "OUT_7") (pintype "passive"))
      (node (ref "U7") (pin "1") (pinfunction "Vin_1") (pintype "power_in"))
      (node (ref "U7") (pin "3") (pinfunction "EN_3") (pintype "passive"))
    )
    (net (code "63") (name "SD_VDD33") (class "Default")
      (node (ref "C4") (pin "1") (pinfunction "1_1") (pintype "passive"))
      (node (ref "J2") (pin "4") (pinfunction "VDD_3V3_4") (pintype "passive"))
      (node (ref "U4") (pin "5") (pinfunction "Vout_5") (pintype "power_in"))
    )
    (net (code "64") (name "VBAT") (class "Default")
      (node (ref "J1") (pin "1") (pinfunction "1_1") (pintype "passive"))
      (node (ref "R13") (pin "1") (pinfunction "1_1") (pintype "passive"))
      (node (ref "R15") (pin "2") (pinfunction "2_2") (pintype "passive"))
      (node (ref "U5") (pin "6") (pinfunction "IN2_6") (pintype "passive"))
      (node (ref "U6") (pin "10") (pinfunction "OUT_10") (pintype "passive"))
    )
    (net (code "65") (name "VDD33") (class "Default")
      (node (ref "C1") (pin "1") (pinfunction "1_1") (pintype "passive"))
      (node (ref "C14") (pin "1") (pinfunction "1_1") (pintype "passive"))
      (node (ref "C2") (pin "1") (pinfunction "1_1") (pintype "passive"))
      (node (ref "C3") (pin "2") (pinfunction "2_2") (pintype "passive"))
      (node (ref "C8") (pin "2") (pinfunction "2_2") (pintype "passive"))
      (node (ref "C9") (pin "2") (pinfunction "2_2") (pintype "passive"))
      (node (ref "H1") (pin "4") (pinfunction "4_4") (pintype "passive"))
      (node (ref "Q2") (pin "3") (pinfunction "C_3") (pintype "passive"))
      (node (ref "R1") (pin "1") (pinfunction "1_1") (pintype "passive"))
      (node (ref "R3") (pin "1") (pinfunction "1_1") (pintype "passive"))
      (node (ref "R8") (pin "1") (pinfunction "1_1") (pintype "passive"))
      (node (ref "R9") (pin "1") (pinfunction "1_1") (pintype "passive"))
      (node (ref "U1") (pin "1") (pinfunction "VDDA_1") (pintype "power_in"))
      (node (ref "U1") (pin "19") (pinfunction "VDD3P3_RTC_19") (pintype "power_in"))
      (node (ref "U1") (pin "3") (pinfunction "VDD3P3_3") (pintype "power_in"))
      (node (ref "U1") (pin "37") (pinfunction "VDD3P3_CPU_37") (pintype "power_in"))
      (node (ref "U1") (pin "4") (pinfunction "VDD3P3_4") (pintype "power_in"))
      (node (ref "U1") (pin "43") (pinfunction "VDDA_43") (pintype "power_in"))
      (node (ref "U1") (pin "46") (pinfunction "VDDA_46") (pintype "power_in"))
      (node (ref "U2") (pin "13") (pinfunction "DVDD_13") (pintype "passive"))
      (node (ref "U2") (pin "23") (pinfunction "DVDD_23") (pintype "passive"))
      (node (ref "U2") (pin "6") (pinfunction "AVDD_6") (pintype "passive"))
      (node (ref "U3") (pin "14") (pinfunction "VCC_14") (pintype "passive"))
      (node (ref "U4") (pin "1") (pinfunction "Vin_1") (pintype "power_in"))
      (node (ref "U7") (pin "5") (pinfunction "Vout_5") (pintype "power_in"))
    )
    (net (code "66") (name "unconnected-(J2-CD-Pad9)") (class "Default")
      (node (ref "J2") (pin "9") (pinfunction "CD_9") (pintype "passive+no_connect"))
    )
    (net (code "67") (name "unconnected-(J2-D1-Pad8)") (class "Default")
      (node (ref "J2") (pin "8") (pinfunction "D1_8") (pintype "passive+no_connect"))
    )
    (net (code "68") (name "unconnected-(J2-D2-Pad1)") (class "Default")
      (node (ref "J2") (pin "1") (pinfunction "D2_1") (pintype "passive+no_connect"))
    )
    (net (code "69") (name "unconnected-(U1-CAP1_NC-Pad48)") (class "Default")
      (node (ref "U1") (pin "48") (pinfunction "CAP1_NC_48") (pintype "passive+no_connect"))
    )
    (net (code "70") (name "unconnected-(U1-CAP2_NC-Pad47)") (class "Default")
      (node (ref "U1") (pin "47") (pinfunction "CAP2_NC_47") (pintype "passive+no_connect"))
    )
    (net (code "71") (name "unconnected-(U1-VDD_SDIO_NC-Pad26)") (class "Default")
      (node (ref "U1") (pin "26") (pinfunction "VDD_SDIO_NC_26") (pintype "passive+no_connect"))
    )
    (net (code "72") (name "unconnected-(U1-XTAL_N_NC-Pad44)") (class "Default")
      (node (ref "U1") (pin "44") (pinfunction "XTAL_N_NC_44") (pintype "passive+no_connect"))
    )
    (net (code "73") (name "unconnected-(U1-XTAL_P_NC-Pad45)") (class "Default")
      (node (ref "U1") (pin "45") (pinfunction "XTAL_P_NC_45") (pintype "passive+no_connect"))
    )
    (net (code "74") (name "unconnected-(U2-D1-Pad10)") (class "Default")
      (node (ref "U2") (pin "10") (pinfunction "D1_10") (pintype "passive+no_connect"))
    )
    (net (code "75") (name "unconnected-(U2-D2-Pad19)") (class "Default")
      (node (ref "U2") (pin "19") (pinfunction "D2_19") (pintype "passive+no_connect"))
    )
    (net (code "76") (name "unconnected-(U2-GPIO8-Pad15)") (class "Default")
      (node (ref "U2") (pin "15") (pinfunction "GPIO8_15") (pintype "passive+no_connect"))
    )
    (net (code "77") (name "unconnected-(U2-GPIO9-Pad17)") (class "Default")
      (node (ref "U2") (pin "17") (pinfunction "GPIO9_17") (pintype "passive+no_connect"))
    )
    (net (code "78") (name "unconnected-(U2-LED-Pad20)") (class "Default")
      (node (ref "U2") (pin "20") (pinfunction "LED_20") (pintype "passive+no_connect"))
    )
    (net (code "79") (name "unconnected-(U2-PMOS-Pad14)") (class "Default")
      (node (ref "U2") (pin "14") (pinfunction "PMOS_14") (pintype "passive+no_connect"))
    )
    (net (code "80") (name "unconnected-(U2-SCL-Pad1)") (class "Default")
      (node (ref "U2") (pin "1") (pinfunction "SCL_1") (pintype "passive+no_connect"))
    )
    (net (code "81") (name "unconnected-(U2-SDA-Pad2)") (class "Default")
      (node (ref "U2") (pin "2") (pinfunction "SDA_2") (pintype "passive+no_connect"))
    )
    (net (code "82") (name "unconnected-(U4-NC-Pad4)") (class "Default")
      (node (ref "U4") (pin "4") (pinfunction "NC_4") (pintype "passive+no_connect"))
    )
    (net (code "83") (name "unconnected-(U5-STAT-Pad1)") (class "Default")
      (node (ref "U5") (pin "1") (pinfunction "STAT_1") (pintype "passive+no_connect"))
    )
    (net (code "84") (name "unconnected-(U6-CHG-Pad8)") (class "Default")
      (node (ref "U6") (pin "8") (pinfunction "CHG_8") (pintype "passive+no_connect"))
    )
    (net (code "85") (name "unconnected-(U6-NC-Pad6)") (class "Default")
      (node (ref "U6") (pin "6") (pinfunction "NC_6") (pintype "passive+no_connect"))
    )
    (net (code "86") (name "unconnected-(U6-PG-Pad5)") (class "Default")
      (node (ref "U6") (pin "5") (pinfunction "PG_5") (pintype "passive+no_connect"))
    )
    (net (code "87") (name "unconnected-(U7-NC-Pad4)") (class "Default")
      (node (ref "U7") (pin "4") (pinfunction "NC_4") (pintype "passive+no_connect"))
    )
  )
)
